# fob.net
KiCad netlist of a schematic drawn in EAGLE
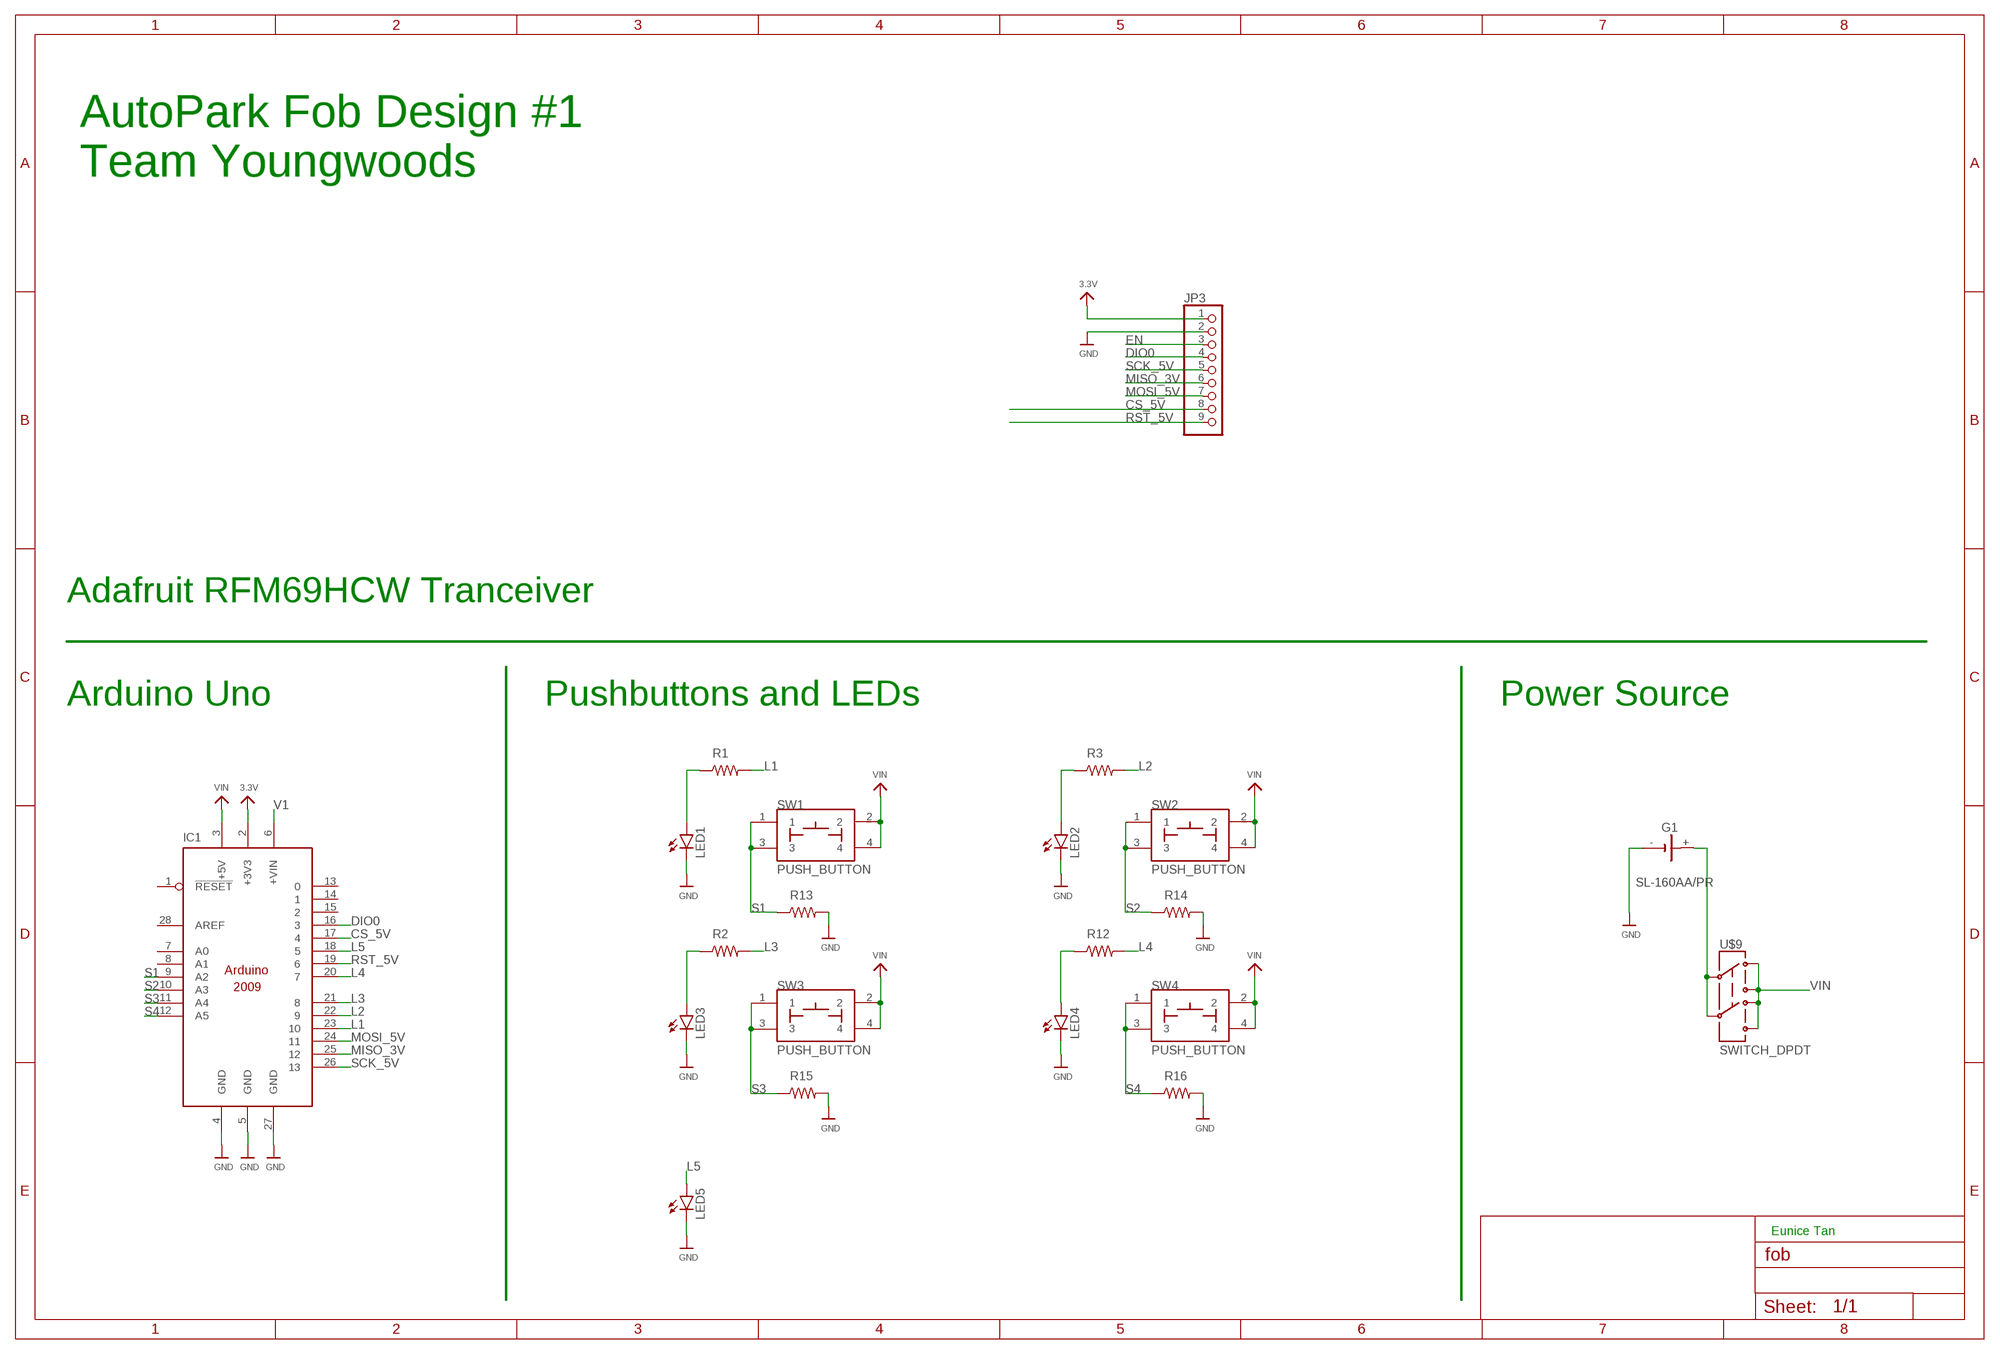
[diagram p0: schematic, sheet 1]

(export (version "E")
  (design (tool "Eeschema 10.0.6"))
  (components
    (comp (ref "G1")
      (value "SL-160AA/PR")
      (footprint "eagle-import:SL-160AA_PR")
      (libsource (lib "eagle-import") (part "SL-160AA/PR"))
    )
    (comp (ref "IC1")
      (value "ARDUINO2009_10")
      (footprint "eagle-import:ARDUINO2009")
      (libsource (lib "eagle-import") (part "ARDUINO2009_10"))
    )
    (comp (ref "JP3")
      (value "HEADER-1X970MIL")
      (footprint "eagle-import:1X09_ROUND_70")
      (libsource (lib "eagle-import") (part "HEADER-1X970MIL"))
    )
    (comp (ref "LED1")
      (value "LED5MM")
      (footprint "eagle-import:LED5MM")
      (libsource (lib "eagle-import") (part "LED5MM"))
    )
    (comp (ref "LED2")
      (value "LED5MM")
      (footprint "eagle-import:LED5MM")
      (libsource (lib "eagle-import") (part "LED5MM"))
    )
    (comp (ref "LED3")
      (value "LED5MM")
      (footprint "eagle-import:LED5MM")
      (libsource (lib "eagle-import") (part "LED5MM"))
    )
    (comp (ref "LED4")
      (value "LED5MM")
      (footprint "eagle-import:LED5MM")
      (libsource (lib "eagle-import") (part "LED5MM"))
    )
    (comp (ref "LED5")
      (value "LED5MM")
      (footprint "eagle-import:LED5MM")
      (libsource (lib "eagle-import") (part "LED5MM"))
    )
    (comp (ref "R1")
      (value "R_R0805")
      (footprint "eagle-import:R0805")
      (libsource (lib "eagle-import") (part "R_R0805"))
    )
    (comp (ref "R2")
      (value "R_R0805")
      (footprint "eagle-import:R0805")
      (libsource (lib "eagle-import") (part "R_R0805"))
    )
    (comp (ref "R3")
      (value "R_R0805")
      (footprint "eagle-import:R0805")
      (libsource (lib "eagle-import") (part "R_R0805"))
    )
    (comp (ref "R12")
      (value "R_R0805")
      (footprint "eagle-import:R0805")
      (libsource (lib "eagle-import") (part "R_R0805"))
    )
    (comp (ref "R13")
      (value "R_R0805")
      (footprint "eagle-import:R0805")
      (libsource (lib "eagle-import") (part "R_R0805"))
    )
    (comp (ref "R14")
      (value "R_R0805")
      (footprint "eagle-import:R0805")
      (libsource (lib "eagle-import") (part "R_R0805"))
    )
    (comp (ref "R15")
      (value "R_R0805")
      (footprint "eagle-import:R0805")
      (libsource (lib "eagle-import") (part "R_R0805"))
    )
    (comp (ref "R16")
      (value "R_R0805")
      (footprint "eagle-import:R0805")
      (libsource (lib "eagle-import") (part "R_R0805"))
    )
    (comp (ref "SW1")
      (value "PUSH_BUTTON")
      (footprint "eagle-import:BUTTON_12.5MM")
      (libsource (lib "eagle-import") (part "PUSH_BUTTON"))
    )
    (comp (ref "SW2")
      (value "PUSH_BUTTON")
      (footprint "eagle-import:BUTTON_12.5MM")
      (libsource (lib "eagle-import") (part "PUSH_BUTTON"))
    )
    (comp (ref "SW3")
      (value "PUSH_BUTTON")
      (footprint "eagle-import:BUTTON_12.5MM")
      (libsource (lib "eagle-import") (part "PUSH_BUTTON"))
    )
    (comp (ref "SW4")
      (value "PUSH_BUTTON")
      (footprint "eagle-import:BUTTON_12.5MM")
      (libsource (lib "eagle-import") (part "PUSH_BUTTON"))
    )
    (comp (ref "U$9")
      (value "SWITCH_DPDT")
      (footprint "eagle-import:JS_DPDT_TH")
      (libsource (lib "eagle-import") (part "SWITCH_DPDT"))
    )
  )
  (nets
    (net (code "1") (name "/CS_5V") (class "Default")
      (node (ref "IC1") (pin "17") (pinfunction "4_17") (pintype "bidirectional"))
      (node (ref "JP3") (pin "8") (pinfunction "8_8") (pintype "passive"))
    )
    (net (code "2") (name "/DIO0") (class "Default")
      (node (ref "IC1") (pin "16") (pinfunction "3_16") (pintype "bidirectional"))
      (node (ref "JP3") (pin "4") (pinfunction "4_4") (pintype "passive"))
    )
    (net (code "3") (name "/EN") (class "Default")
      (node (ref "JP3") (pin "3") (pinfunction "3_3") (pintype "passive"))
    )
    (net (code "4") (name "/L1") (class "Default")
      (node (ref "IC1") (pin "23") (pinfunction "10_23") (pintype "bidirectional"))
      (node (ref "R1") (pin "2") (pinfunction "2_2") (pintype "passive"))
    )
    (net (code "5") (name "/L2") (class "Default")
      (node (ref "IC1") (pin "22") (pinfunction "9_22") (pintype "bidirectional"))
      (node (ref "R3") (pin "2") (pinfunction "2_2") (pintype "passive"))
    )
    (net (code "6") (name "/L3") (class "Default")
      (node (ref "IC1") (pin "21") (pinfunction "8_21") (pintype "bidirectional"))
      (node (ref "R2") (pin "2") (pinfunction "2_2") (pintype "passive"))
    )
    (net (code "7") (name "/L4") (class "Default")
      (node (ref "IC1") (pin "20") (pinfunction "7_20") (pintype "bidirectional"))
      (node (ref "R12") (pin "2") (pinfunction "2_2") (pintype "passive"))
    )
    (net (code "8") (name "/L5") (class "Default")
      (node (ref "IC1") (pin "18") (pinfunction "5_18") (pintype "bidirectional"))
      (node (ref "LED5") (pin "A") (pinfunction "A_A") (pintype "passive"))
    )
    (net (code "9") (name "/MISO_3V") (class "Default")
      (node (ref "IC1") (pin "25") (pinfunction "12_25") (pintype "bidirectional"))
      (node (ref "JP3") (pin "6") (pinfunction "6_6") (pintype "passive"))
    )
    (net (code "10") (name "/MOSI_5V") (class "Default")
      (node (ref "IC1") (pin "24") (pinfunction "11_24") (pintype "bidirectional"))
      (node (ref "JP3") (pin "7") (pinfunction "7_7") (pintype "passive"))
    )
    (net (code "12") (name "/RST_5V") (class "Default")
      (node (ref "IC1") (pin "19") (pinfunction "6_19") (pintype "bidirectional"))
      (node (ref "JP3") (pin "9") (pinfunction "9_9") (pintype "passive"))
    )
    (net (code "13") (name "/S1") (class "Default")
      (node (ref "IC1") (pin "9") (pinfunction "A2_9") (pintype "bidirectional"))
      (node (ref "R13") (pin "1") (pinfunction "1_1") (pintype "passive"))
      (node (ref "SW1") (pin "1") (pinfunction "1_1") (pintype "bidirectional"))
      (node (ref "SW1") (pin "3") (pinfunction "3_3") (pintype "bidirectional"))
    )
    (net (code "14") (name "/S2") (class "Default")
      (node (ref "IC1") (pin "10") (pinfunction "A3_10") (pintype "bidirectional"))
      (node (ref "R14") (pin "1") (pinfunction "1_1") (pintype "passive"))
      (node (ref "SW2") (pin "1") (pinfunction "1_1") (pintype "bidirectional"))
      (node (ref "SW2") (pin "3") (pinfunction "3_3") (pintype "bidirectional"))
    )
    (net (code "15") (name "/S3") (class "Default")
      (node (ref "IC1") (pin "11") (pinfunction "A4_11") (pintype "bidirectional"))
      (node (ref "R15") (pin "1") (pinfunction "1_1") (pintype "passive"))
      (node (ref "SW3") (pin "1") (pinfunction "1_1") (pintype "bidirectional"))
      (node (ref "SW3") (pin "3") (pinfunction "3_3") (pintype "bidirectional"))
    )
    (net (code "16") (name "/S4") (class "Default")
      (node (ref "IC1") (pin "12") (pinfunction "A5_12") (pintype "bidirectional"))
      (node (ref "R16") (pin "1") (pinfunction "1_1") (pintype "passive"))
      (node (ref "SW4") (pin "1") (pinfunction "1_1") (pintype "bidirectional"))
      (node (ref "SW4") (pin "3") (pinfunction "3_3") (pintype "bidirectional"))
    )
    (net (code "17") (name "/SCK_5V") (class "Default")
      (node (ref "IC1") (pin "26") (pinfunction "13_26") (pintype "bidirectional"))
      (node (ref "JP3") (pin "5") (pinfunction "5_5") (pintype "passive"))
    )
    (net (code "18") (name "/V1") (class "Default")
      (node (ref "IC1") (pin "6") (pinfunction "+VIN_6") (pintype "bidirectional"))
    )
    (net (code "19") (name "3.3V") (class "Default")
      (node (ref "IC1") (pin "2") (pinfunction "+3V3_2") (pintype "power_in"))
      (node (ref "JP3") (pin "1") (pinfunction "1_1") (pintype "passive"))
    )
    (net (code "20") (name "GND") (class "Default")
      (node (ref "G1") (pin "-") (pinfunction "-_-") (pintype "passive"))
      (node (ref "IC1") (pin "27") (pinfunction "GND_27") (pintype "power_in"))
      (node (ref "IC1") (pin "4") (pinfunction "GND_4") (pintype "power_in"))
      (node (ref "IC1") (pin "5") (pinfunction "GND_5") (pintype "power_in"))
      (node (ref "JP3") (pin "2") (pinfunction "2_2") (pintype "passive"))
      (node (ref "LED1") (pin "K") (pinfunction "C_K") (pintype "passive"))
      (node (ref "LED2") (pin "K") (pinfunction "C_K") (pintype "passive"))
      (node (ref "LED3") (pin "K") (pinfunction "C_K") (pintype "passive"))
      (node (ref "LED4") (pin "K") (pinfunction "C_K") (pintype "passive"))
      (node (ref "LED5") (pin "K") (pinfunction "C_K") (pintype "passive"))
      (node (ref "R13") (pin "2") (pinfunction "2_2") (pintype "passive"))
      (node (ref "R14") (pin "2") (pinfunction "2_2") (pintype "passive"))
      (node (ref "R15") (pin "2") (pinfunction "2_2") (pintype "passive"))
      (node (ref "R16") (pin "2") (pinfunction "2_2") (pintype "passive"))
    )
    (net (code "21") (name "Net-(G1-Pad+)") (class "Default")
      (node (ref "G1") (pin "+") (pinfunction "+_+") (pintype "passive"))
      (node (ref "U$9") (pin "2") (pinfunction "2_2") (pintype "bidirectional"))
      (node (ref "U$9") (pin "5") (pinfunction "5_5") (pintype "bidirectional"))
    )
    (net (code "22") (name "Net-(LED1-PadA)") (class "Default")
      (node (ref "LED1") (pin "A") (pinfunction "A_A") (pintype "passive"))
      (node (ref "R1") (pin "1") (pinfunction "1_1") (pintype "passive"))
    )
    (net (code "23") (name "Net-(LED2-PadA)") (class "Default")
      (node (ref "LED2") (pin "A") (pinfunction "A_A") (pintype "passive"))
      (node (ref "R3") (pin "1") (pinfunction "1_1") (pintype "passive"))
    )
    (net (code "24") (name "Net-(LED3-PadA)") (class "Default")
      (node (ref "LED3") (pin "A") (pinfunction "A_A") (pintype "passive"))
      (node (ref "R2") (pin "1") (pinfunction "1_1") (pintype "passive"))
    )
    (net (code "25") (name "Net-(LED4-PadA)") (class "Default")
      (node (ref "LED4") (pin "A") (pinfunction "A_A") (pintype "passive"))
      (node (ref "R12") (pin "1") (pinfunction "1_1") (pintype "passive"))
    )
    (net (code "26") (name "VIN") (class "Default")
      (node (ref "IC1") (pin "3") (pinfunction "+5V_3") (pintype "power_in"))
      (node (ref "SW1") (pin "2") (pinfunction "2_2") (pintype "bidirectional"))
      (node (ref "SW1") (pin "4") (pinfunction "4_4") (pintype "bidirectional"))
      (node (ref "SW2") (pin "2") (pinfunction "2_2") (pintype "bidirectional"))
      (node (ref "SW2") (pin "4") (pinfunction "4_4") (pintype "bidirectional"))
      (node (ref "SW3") (pin "2") (pinfunction "2_2") (pintype "bidirectional"))
      (node (ref "SW3") (pin "4") (pinfunction "4_4") (pintype "bidirectional"))
      (node (ref "SW4") (pin "2") (pinfunction "2_2") (pintype "bidirectional"))
      (node (ref "SW4") (pin "4") (pinfunction "4_4") (pintype "bidirectional"))
      (node (ref "U$9") (pin "1") (pinfunction "1_1") (pintype "bidirectional"))
      (node (ref "U$9") (pin "3") (pinfunction "3_3") (pintype "bidirectional"))
      (node (ref "U$9") (pin "4") (pinfunction "4_4") (pintype "bidirectional"))
      (node (ref "U$9") (pin "6") (pinfunction "6_6") (pintype "bidirectional"))
    )
    (net (code "27") (name "unconnected-(IC1-0-Pad13)") (class "Default")
      (node (ref "IC1") (pin "13") (pinfunction "0_13") (pintype "bidirectional"))
    )
    (net (code "28") (name "unconnected-(IC1-1-Pad14)") (class "Default")
      (node (ref "IC1") (pin "14") (pinfunction "1_14") (pintype "bidirectional"))
    )
    (net (code "29") (name "unconnected-(IC1-2-Pad15)") (class "Default")
      (node (ref "IC1") (pin "15") (pinfunction "2_15") (pintype "bidirectional"))
    )
    (net (code "30") (name "unconnected-(IC1-A0-Pad7)") (class "Default")
      (node (ref "IC1") (pin "7") (pinfunction "A0_7") (pintype "bidirectional"))
    )
    (net (code "31") (name "unconnected-(IC1-A1-Pad8)") (class "Default")
      (node (ref "IC1") (pin "8") (pinfunction "A1_8") (pintype "bidirectional"))
    )
    (net (code "32") (name "unconnected-(IC1-AREF-Pad28)") (class "Default")
      (node (ref "IC1") (pin "28") (pinfunction "AREF_28") (pintype "bidirectional"))
    )
    (net (code "33") (name "unconnected-(IC1-~{RESET}-Pad1)") (class "Default")
      (node (ref "IC1") (pin "1") (pinfunction "~{RESET}_1") (pintype "bidirectional"))
    )
  )
)
